# SCH_DTNEA-Z-AXIS-PRESS-MONITOR-TRANSMITT.net
KiCad netlist of a schematic drawn in EasyEDA
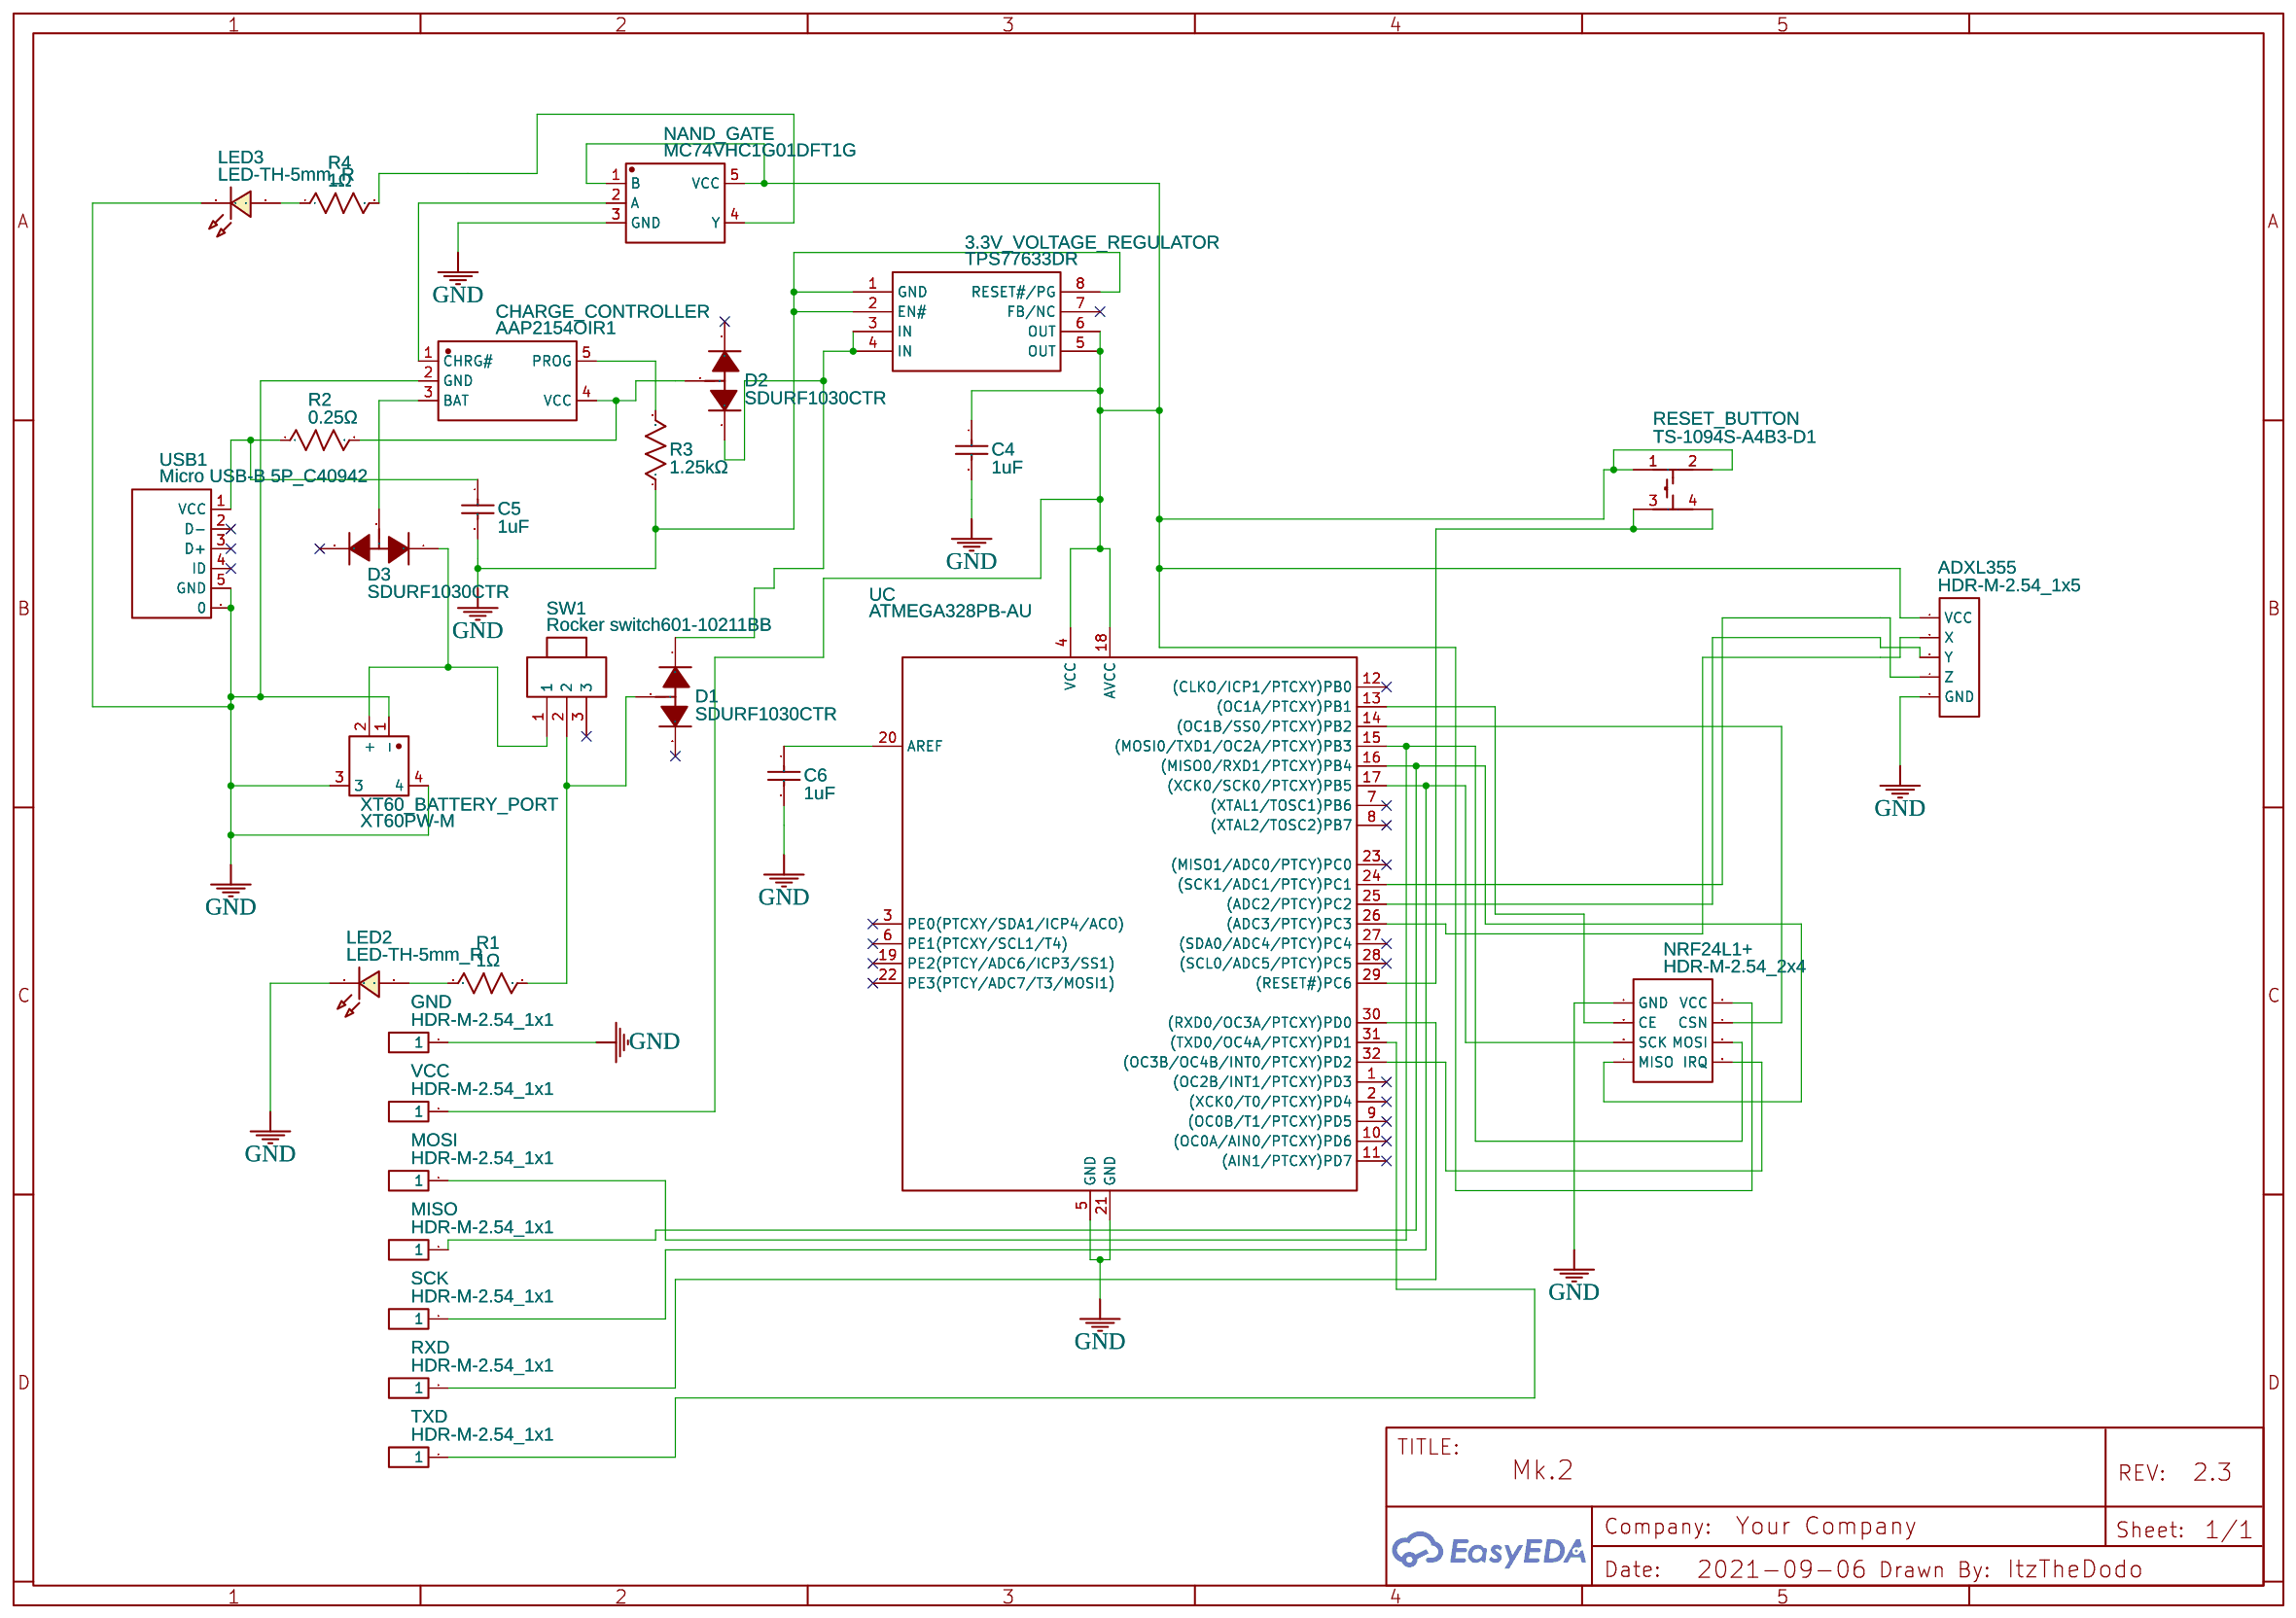
[diagram p0: schematic sheet]

(export (version "E")
  (design (tool "Eeschema 10.0.6"))
  (components
    (comp (ref "3.3V_VOLTAGE_REGULATOR")
      (value "TPS77633DR")
      (fields (field (name "BOM_Supplier Part") "C130078"))
      (libsource (lib "") (part "TPS77633DR"))
    )
    (comp (ref "ADXL355")
      (value "HDR-M-2.54_1x5")
      (fields (field (name "BOM_Supplier Part") "C358687"))
      (libsource (lib "") (part "HDR-M-2.54_1x5"))
    )
    (comp (ref "C4")
      (value "1uF")
      (fields
        (field (name "BOM_Manufacturer Part") "0603F105M250NT")
        (field (name "BOM_Supplier Part") "C36577")
      )
      (libsource (lib "") (part "0603F105M250NT"))
    )
    (comp (ref "C5")
      (value "1uF")
      (fields
        (field (name "BOM_Manufacturer Part") "0603F105M250NT")
        (field (name "BOM_Supplier Part") "C36577")
      )
      (libsource (lib "") (part "0603F105M250NT"))
    )
    (comp (ref "C6")
      (value "1uF")
      (fields
        (field (name "BOM_Manufacturer Part") "0603F105M250NT")
        (field (name "BOM_Supplier Part") "C36577")
      )
      (libsource (lib "") (part "0603F105M250NT"))
    )
    (comp (ref "CHARGE_CONTROLLER")
      (value "AAP2154OIR1")
      (fields (field (name "BOM_Supplier Part") "C370749"))
      (libsource (lib "") (part "AAP2154OIR1"))
    )
    (comp (ref "D1")
      (value "SDURF1030CTR")
      (fields (field (name "BOM_Supplier Part") "C260371"))
      (libsource (lib "") (part "SDURF1030CTR_1"))
    )
    (comp (ref "D2")
      (value "SDURF1030CTR")
      (fields (field (name "BOM_Supplier Part") "C260371"))
      (libsource (lib "") (part "SDURF1030CTR_1"))
    )
    (comp (ref "D3")
      (value "SDURF1030CTR")
      (fields (field (name "BOM_Supplier Part") "C260371"))
      (libsource (lib "") (part "SDURF1030CTR"))
    )
    (comp (ref "GND")
      (value "HDR-M-2.54_1x1")
      (fields (field (name "BOM_Supplier Part") "C81276"))
      (libsource (lib "") (part "HDR-M-2.54_1x1_3"))
    )
    (comp (ref "LED2")
      (value "LED-TH-5mm_R")
      (fields
        (field (name "BOM_Manufacturer Part") "333-2SURD/S530-A3")
        (field (name "BOM_Supplier Part") "C87271")
      )
      (libsource (lib "") (part "LED-TH-5mm_R"))
    )
    (comp (ref "LED3")
      (value "LED-TH-5mm_R")
      (fields
        (field (name "BOM_Manufacturer Part") "333-2SURD/S530-A3")
        (field (name "BOM_Supplier Part") "C87271")
      )
      (libsource (lib "") (part "LED-TH-5mm_R"))
    )
    (comp (ref "MISO")
      (value "HDR-M-2.54_1x1")
      (fields (field (name "BOM_Supplier Part") "C81276"))
      (libsource (lib "") (part "HDR-M-2.54_1x1_6"))
    )
    (comp (ref "MOSI")
      (value "HDR-M-2.54_1x1")
      (fields (field (name "BOM_Supplier Part") "C81276"))
      (libsource (lib "") (part "HDR-M-2.54_1x1"))
    )
    (comp (ref "NAND_GATE")
      (value "MC74VHC1G01DFT1G")
      (fields (field (name "BOM_Supplier Part") "C150244"))
      (libsource (lib "") (part "MC74VHC1G01DFT1G"))
    )
    (comp (ref "NRF24L1+")
      (value "HDR-M-2.54_2x4")
      (fields (field (name "BOM_Supplier Part") "C58363"))
      (libsource (lib "") (part "HDR-M-2.54_2x4"))
    )
    (comp (ref "R1") (value "1Ω") (libsource (lib "") (part "R_0603_US")))
    (comp (ref "R2") (value "0.25Ω") (libsource (lib "") (part "R_0603_US")))
    (comp (ref "R3") (value "1.25kΩ") (libsource (lib "") (part "R_0603_US_1")))
    (comp (ref "R4") (value "1Ω") (libsource (lib "") (part "R_0603_US")))
    (comp (ref "RESET_BUTTON")
      (value "TS-1094S-A4B3-D1")
      (fields (field (name "BOM_Supplier Part") "C492972"))
      (libsource (lib "") (part "TS-1094S-A4B3-D1"))
    )
    (comp (ref "RXD")
      (value "HDR-M-2.54_1x1")
      (fields (field (name "BOM_Supplier Part") "C81276"))
      (libsource (lib "") (part "HDR-M-2.54_1x1_2"))
    )
    (comp (ref "SCK")
      (value "HDR-M-2.54_1x1")
      (fields (field (name "BOM_Supplier Part") "C81276"))
      (libsource (lib "") (part "HDR-M-2.54_1x1_5"))
    )
    (comp (ref "SW1")
      (value "Rocker switch601-10211BB")
      (fields (field (name "BOM_Supplier Part") "C67849"))
      (libsource (lib "") (part "Rocker switch601-10211BB"))
    )
    (comp (ref "TXD")
      (value "HDR-M-2.54_1x1")
      (fields (field (name "BOM_Supplier Part") "C81276"))
      (libsource (lib "") (part "HDR-M-2.54_1x1_1"))
    )
    (comp (ref "UC")
      (value "ATMEGA328PB-AU")
      (fields (field (name "BOM_Supplier Part") "C132230"))
      (libsource (lib "") (part "ATMEGA328PB-AU"))
    )
    (comp (ref "USB1")
      (value "Micro USB-B 5P_C40942")
      (fields (field (name "BOM_Supplier Part") "C40942"))
      (libsource (lib "") (part "Micro USB-B 5P_C40942"))
    )
    (comp (ref "VCC")
      (value "HDR-M-2.54_1x1")
      (fields (field (name "BOM_Supplier Part") "C81276"))
      (libsource (lib "") (part "HDR-M-2.54_1x1_4"))
    )
    (comp (ref "XT60_BATTERY_PORT")
      (value "XT60PW-M")
      (fields (field (name "BOM_Supplier Part") "C98732"))
      (libsource (lib "") (part "XT60PW-M"))
    )
  )
  (nets
    (net (code "1") (name "GND") (class "Default")
      (node (ref "3.3V_VOLTAGE_REGULATOR") (pin "1") (pinfunction "GND_1") (pintype "passive"))
      (node (ref "3.3V_VOLTAGE_REGULATOR") (pin "2") (pinfunction "EN#_2") (pintype "unspecified"))
      (node (ref "3.3V_VOLTAGE_REGULATOR") (pin "8") (pinfunction "RESET#/PG_8") (pintype "unspecified"))
      (node (ref "ADXL355") (pin "5") (pinfunction "GND_5") (pintype "unspecified"))
      (node (ref "C4") (pin "2") (pinfunction "2_2") (pintype "input"))
      (node (ref "C5") (pin "2") (pinfunction "2_2") (pintype "input"))
      (node (ref "C6") (pin "2") (pinfunction "2_2") (pintype "input"))
      (node (ref "CHARGE_CONTROLLER") (pin "2") (pinfunction "GND_2") (pintype "unspecified"))
      (node (ref "GND") (pin "1") (pinfunction "1_1") (pintype "input"))
      (node (ref "LED2") (pin "2") (pinfunction "2_2") (pintype "unspecified"))
      (node (ref "LED3") (pin "2") (pinfunction "2_2") (pintype "unspecified"))
      (node (ref "NAND_GATE") (pin "3") (pinfunction "GND_3") (pintype "unspecified"))
      (node (ref "NRF24L1+") (pin "1") (pinfunction "GND_1") (pintype "unspecified"))
      (node (ref "R3") (pin "1") (pinfunction "1_1") (pintype "unspecified"))
      (node (ref "UC") (pin "21") (pinfunction "GND_21") (pintype "bidirectional"))
      (node (ref "UC") (pin "5") (pinfunction "GND_5") (pintype "bidirectional"))
      (node (ref "USB1") (pin "0") (pinfunction "0_0") (pintype "input"))
      (node (ref "USB1") (pin "5") (pinfunction "GND_5") (pintype "input"))
      (node (ref "XT60_BATTERY_PORT") (pin "1") (pinfunction "-_1") (pintype "unspecified"))
      (node (ref "XT60_BATTERY_PORT") (pin "3") (pinfunction "3_3") (pintype "unspecified"))
      (node (ref "XT60_BATTERY_PORT") (pin "4") (pinfunction "4_4") (pintype "unspecified"))
    )
    (net (code "2") (name "Net-(3.3V_VOLTAGE_REGULATOR-IN-Pad3)") (class "Default")
      (node (ref "3.3V_VOLTAGE_REGULATOR") (pin "3") (pinfunction "IN_3") (pintype "passive"))
      (node (ref "3.3V_VOLTAGE_REGULATOR") (pin "4") (pinfunction "IN_4") (pintype "passive"))
      (node (ref "D1") (pin "1") (pinfunction "C_1") (pintype "unspecified"))
      (node (ref "D2") (pin "3") (pinfunction "C_3") (pintype "unspecified"))
    )
    (net (code "3") (name "Net-(ADXL355-VCC)") (class "Default")
      (node (ref "3.3V_VOLTAGE_REGULATOR") (pin "5") (pinfunction "OUT_5") (pintype "passive"))
      (node (ref "3.3V_VOLTAGE_REGULATOR") (pin "6") (pinfunction "OUT_6") (pintype "passive"))
      (node (ref "ADXL355") (pin "1") (pinfunction "VCC_1") (pintype "unspecified"))
      (node (ref "C4") (pin "1") (pinfunction "1_1") (pintype "input"))
      (node (ref "NAND_GATE") (pin "1") (pinfunction "B_1") (pintype "unspecified"))
      (node (ref "NAND_GATE") (pin "5") (pinfunction "VCC_5") (pintype "unspecified"))
      (node (ref "NRF24L1+") (pin "2") (pinfunction "VCC_2") (pintype "unspecified"))
      (node (ref "RESET_BUTTON") (pin "1") (pinfunction "1_1") (pintype "unspecified"))
      (node (ref "RESET_BUTTON") (pin "2") (pinfunction "2_2") (pintype "unspecified"))
      (node (ref "UC") (pin "18") (pinfunction "AVCC_18") (pintype "bidirectional"))
      (node (ref "UC") (pin "4") (pinfunction "VCC_4") (pintype "bidirectional"))
      (node (ref "VCC") (pin "1") (pinfunction "1_1") (pintype "input"))
    )
    (net (code "4") (name "Net-(ADXL355-X)") (class "Default")
      (node (ref "ADXL355") (pin "2") (pinfunction "X_2") (pintype "unspecified"))
      (node (ref "UC") (pin "26") (pinfunction "(ADC3/PTCY)PC3_26") (pintype "bidirectional"))
    )
    (net (code "5") (name "Net-(ADXL355-Y)") (class "Default")
      (node (ref "ADXL355") (pin "3") (pinfunction "Y_3") (pintype "unspecified"))
      (node (ref "UC") (pin "25") (pinfunction "(ADC2/PTCY)PC2_25") (pintype "bidirectional"))
    )
    (net (code "6") (name "Net-(ADXL355-Z)") (class "Default")
      (node (ref "ADXL355") (pin "4") (pinfunction "Z_4") (pintype "unspecified"))
      (node (ref "UC") (pin "24") (pinfunction "(SCK1/ADC1/PTCY)PC1_24") (pintype "bidirectional"))
    )
    (net (code "7") (name "Net-(CHARGE_CONTROLLER-BAT)") (class "Default")
      (node (ref "CHARGE_CONTROLLER") (pin "3") (pinfunction "BAT_3") (pintype "unspecified"))
      (node (ref "D3") (pin "2") (pinfunction "A_2") (pintype "unspecified"))
    )
    (net (code "8") (name "Net-(CHARGE_CONTROLLER-CHRG#)") (class "Default")
      (node (ref "CHARGE_CONTROLLER") (pin "1") (pinfunction "CHRG#_1") (pintype "unspecified"))
      (node (ref "NAND_GATE") (pin "2") (pinfunction "A_2") (pintype "unspecified"))
    )
    (net (code "9") (name "Net-(CHARGE_CONTROLLER-PROG)") (class "Default")
      (node (ref "CHARGE_CONTROLLER") (pin "5") (pinfunction "PROG_5") (pintype "unspecified"))
      (node (ref "R3") (pin "2") (pinfunction "2_2") (pintype "unspecified"))
    )
    (net (code "10") (name "Net-(CHARGE_CONTROLLER-VCC)") (class "Default")
      (node (ref "CHARGE_CONTROLLER") (pin "4") (pinfunction "VCC_4") (pintype "unspecified"))
      (node (ref "D2") (pin "2") (pinfunction "A_2") (pintype "unspecified"))
      (node (ref "R2") (pin "2") (pinfunction "2_2") (pintype "unspecified"))
    )
    (net (code "11") (name "Net-(D1-A)") (class "Default")
      (node (ref "D1") (pin "2") (pinfunction "A_2") (pintype "unspecified"))
      (node (ref "R1") (pin "2") (pinfunction "2_2") (pintype "unspecified"))
      (node (ref "SW1") (pin "2") (pinfunction "2_2") (pintype "unspecified"))
    )
    (net (code "12") (name "Net-(LED2-Pad1)") (class "Default")
      (node (ref "LED2") (pin "1") (pinfunction "1_1") (pintype "unspecified"))
      (node (ref "R1") (pin "1") (pinfunction "1_1") (pintype "unspecified"))
    )
    (net (code "13") (name "Net-(LED3-Pad1)") (class "Default")
      (node (ref "LED3") (pin "1") (pinfunction "1_1") (pintype "unspecified"))
      (node (ref "R4") (pin "1") (pinfunction "1_1") (pintype "unspecified"))
    )
    (net (code "14") (name "Net-(NAND_GATE-Y)") (class "Default")
      (node (ref "NAND_GATE") (pin "4") (pinfunction "Y_4") (pintype "unspecified"))
      (node (ref "R4") (pin "2") (pinfunction "2_2") (pintype "unspecified"))
    )
    (net (code "15") (name "Net-(NRF24L1+-CE)") (class "Default")
      (node (ref "NRF24L1+") (pin "3") (pinfunction "CE_3") (pintype "unspecified"))
      (node (ref "UC") (pin "13") (pinfunction "(OC1A/PTCXY)PB1_13") (pintype "bidirectional"))
    )
    (net (code "16") (name "Net-(NRF24L1+-CSN)") (class "Default")
      (node (ref "NRF24L1+") (pin "4") (pinfunction "CSN_4") (pintype "unspecified"))
      (node (ref "UC") (pin "14") (pinfunction "(OC1B/SS0/PTCXY)PB2_14") (pintype "bidirectional"))
    )
    (net (code "17") (name "Net-(NRF24L1+-IRQ)") (class "Default")
      (node (ref "NRF24L1+") (pin "8") (pinfunction "IRQ_8") (pintype "unspecified"))
      (node (ref "UC") (pin "32") (pinfunction "(OC3B/OC4B/INT0/PTCXY)PD2_32") (pintype "bidirectional"))
    )
    (net (code "18") (name "Net-(NRF24L1+-MISO)") (class "Default")
      (node (ref "MISO") (pin "1") (pinfunction "1_1") (pintype "input"))
      (node (ref "NRF24L1+") (pin "7") (pinfunction "MISO_7") (pintype "unspecified"))
      (node (ref "UC") (pin "16") (pinfunction "(MISO0/RXD1/PTCXY)PB4_16") (pintype "bidirectional"))
    )
    (net (code "19") (name "Net-(NRF24L1+-MOSI)") (class "Default")
      (node (ref "MOSI") (pin "1") (pinfunction "1_1") (pintype "input"))
      (node (ref "NRF24L1+") (pin "6") (pinfunction "MOSI_6") (pintype "unspecified"))
      (node (ref "UC") (pin "15") (pinfunction "(MOSI0/TXD1/OC2A/PTCXY)PB3_15") (pintype "bidirectional"))
    )
    (net (code "20") (name "Net-(NRF24L1+-SCK)") (class "Default")
      (node (ref "NRF24L1+") (pin "5") (pinfunction "SCK_5") (pintype "unspecified"))
      (node (ref "SCK") (pin "1") (pinfunction "1_1") (pintype "input"))
      (node (ref "UC") (pin "17") (pinfunction "(XCK0/SCK0/PTCXY)PB5_17") (pintype "bidirectional"))
    )
    (net (code "21") (name "Net-(UC-(RESET#)PC6)") (class "Default")
      (node (ref "RESET_BUTTON") (pin "3") (pinfunction "3_3") (pintype "unspecified"))
      (node (ref "RESET_BUTTON") (pin "4") (pinfunction "4_4") (pintype "unspecified"))
      (node (ref "UC") (pin "29") (pinfunction "(RESET#)PC6_29") (pintype "bidirectional"))
    )
    (net (code "22") (name "Net-(UC-(RXD0{slash}OC3A{slash}PTCXY)PD0)") (class "Default")
      (node (ref "RXD") (pin "1") (pinfunction "1_1") (pintype "input"))
      (node (ref "UC") (pin "30") (pinfunction "(RXD0/OC3A/PTCXY)PD0_30") (pintype "bidirectional"))
    )
    (net (code "23") (name "Net-(UC-(TXD0{slash}OC4A{slash}PTCXY)PD1)") (class "Default")
      (node (ref "TXD") (pin "1") (pinfunction "1_1") (pintype "input"))
      (node (ref "UC") (pin "31") (pinfunction "(TXD0/OC4A/PTCXY)PD1_31") (pintype "bidirectional"))
    )
    (net (code "24") (name "Net-(UC-AREF)") (class "Default")
      (node (ref "C6") (pin "1") (pinfunction "1_1") (pintype "input"))
      (node (ref "UC") (pin "20") (pinfunction "AREF_20") (pintype "bidirectional"))
    )
    (net (code "25") (name "Net-(USB1-VCC)") (class "Default")
      (node (ref "C5") (pin "1") (pinfunction "1_1") (pintype "input"))
      (node (ref "R2") (pin "1") (pinfunction "1_1") (pintype "unspecified"))
      (node (ref "USB1") (pin "1") (pinfunction "VCC_1") (pintype "input"))
    )
    (net (code "26") (name "Net-(XT60_BATTERY_PORT-+)") (class "Default")
      (node (ref "D3") (pin "1") (pinfunction "C_1") (pintype "unspecified"))
      (node (ref "SW1") (pin "1") (pinfunction "1_1") (pintype "unspecified"))
      (node (ref "XT60_BATTERY_PORT") (pin "2") (pinfunction "+_2") (pintype "unspecified"))
    )
    (net (code "27") (name "unconnected-(3.3V_VOLTAGE_REGULATOR-FB{slash}NC-Pad7)") (class "Default")
      (node (ref "3.3V_VOLTAGE_REGULATOR") (pin "7") (pinfunction "FB/NC_7") (pintype "unspecified+no_connect"))
    )
    (net (code "28") (name "unconnected-(D1-C-Pad3)") (class "Default")
      (node (ref "D1") (pin "3") (pinfunction "C_3") (pintype "unspecified+no_connect"))
    )
    (net (code "29") (name "unconnected-(D2-C-Pad1)") (class "Default")
      (node (ref "D2") (pin "1") (pinfunction "C_1") (pintype "unspecified+no_connect"))
    )
    (net (code "30") (name "unconnected-(D3-C-Pad3)") (class "Default")
      (node (ref "D3") (pin "3") (pinfunction "C_3") (pintype "unspecified+no_connect"))
    )
    (net (code "31") (name "unconnected-(SW1-Pad3)") (class "Default")
      (node (ref "SW1") (pin "3") (pinfunction "3_3") (pintype "unspecified+no_connect"))
    )
    (net (code "32") (name "unconnected-(UC-(AIN1{slash}PTCXY)PD7-Pad11)") (class "Default")
      (node (ref "UC") (pin "11") (pinfunction "(AIN1/PTCXY)PD7_11") (pintype "bidirectional+no_connect"))
    )
    (net (code "33") (name "unconnected-(UC-(CLKO{slash}ICP1{slash}PTCXY)PB0-Pad12)") (class "Default")
      (node (ref "UC") (pin "12") (pinfunction "(CLKO/ICP1/PTCXY)PB0_12") (pintype "bidirectional+no_connect"))
    )
    (net (code "34") (name "unconnected-(UC-(MISO1{slash}ADC0{slash}PTCY)PC0-Pad23)") (class "Default")
      (node (ref "UC") (pin "23") (pinfunction "(MISO1/ADC0/PTCY)PC0_23") (pintype "bidirectional+no_connect"))
    )
    (net (code "35") (name "unconnected-(UC-(OC0A{slash}AIN0{slash}PTCXY)PD6-Pad10)") (class "Default")
      (node (ref "UC") (pin "10") (pinfunction "(OC0A/AIN0/PTCXY)PD6_10") (pintype "bidirectional+no_connect"))
    )
    (net (code "36") (name "unconnected-(UC-(OC0B{slash}T1{slash}PTCXY)PD5-Pad9)") (class "Default")
      (node (ref "UC") (pin "9") (pinfunction "(OC0B/T1/PTCXY)PD5_9") (pintype "bidirectional+no_connect"))
    )
    (net (code "37") (name "unconnected-(UC-(OC2B{slash}INT1{slash}PTCXY)PD3-Pad1)") (class "Default")
      (node (ref "UC") (pin "1") (pinfunction "(OC2B/INT1/PTCXY)PD3_1") (pintype "bidirectional+no_connect"))
    )
    (net (code "38") (name "unconnected-(UC-(SCL0{slash}ADC5{slash}PTCY)PC5-Pad28)") (class "Default")
      (node (ref "UC") (pin "28") (pinfunction "(SCL0/ADC5/PTCY)PC5_28") (pintype "bidirectional+no_connect"))
    )
    (net (code "39") (name "unconnected-(UC-(SDA0{slash}ADC4{slash}PTCY)PC4-Pad27)") (class "Default")
      (node (ref "UC") (pin "27") (pinfunction "(SDA0/ADC4/PTCY)PC4_27") (pintype "bidirectional+no_connect"))
    )
    (net (code "40") (name "unconnected-(UC-(XCK0{slash}T0{slash}PTCXY)PD4-Pad2)") (class "Default")
      (node (ref "UC") (pin "2") (pinfunction "(XCK0/T0/PTCXY)PD4_2") (pintype "bidirectional+no_connect"))
    )
    (net (code "41") (name "unconnected-(UC-(XTAL1{slash}TOSC1)PB6-Pad7)") (class "Default")
      (node (ref "UC") (pin "7") (pinfunction "(XTAL1/TOSC1)PB6_7") (pintype "bidirectional+no_connect"))
    )
    (net (code "42") (name "unconnected-(UC-(XTAL2{slash}TOSC2)PB7-Pad8)") (class "Default")
      (node (ref "UC") (pin "8") (pinfunction "(XTAL2/TOSC2)PB7_8") (pintype "bidirectional+no_connect"))
    )
    (net (code "43") (name "unconnected-(UC-PE0(PTCXY{slash}SDA1{slash}ICP4{slash}ACO)-Pad3)") (class "Default")
      (node (ref "UC") (pin "3") (pinfunction "PE0(PTCXY/SDA1/ICP4/ACO)_3") (pintype "bidirectional+no_connect"))
    )
    (net (code "44") (name "unconnected-(UC-PE1(PTCXY{slash}SCL1{slash}T4)-Pad6)") (class "Default")
      (node (ref "UC") (pin "6") (pinfunction "PE1(PTCXY/SCL1/T4)_6") (pintype "bidirectional+no_connect"))
    )
    (net (code "45") (name "unconnected-(UC-PE2(PTCY{slash}ADC6{slash}ICP3{slash}SS1)-Pad19)") (class "Default")
      (node (ref "UC") (pin "19") (pinfunction "PE2(PTCY/ADC6/ICP3/SS1)_19") (pintype "bidirectional+no_connect"))
    )
    (net (code "46") (name "unconnected-(UC-PE3(PTCY{slash}ADC7{slash}T3{slash}MOSI1)-Pad22)") (class "Default")
      (node (ref "UC") (pin "22") (pinfunction "PE3(PTCY/ADC7/T3/MOSI1)_22") (pintype "bidirectional+no_connect"))
    )
    (net (code "47") (name "unconnected-(USB1-D+-Pad3)") (class "Default")
      (node (ref "USB1") (pin "3") (pinfunction "D+_3") (pintype "input+no_connect"))
    )
    (net (code "48") (name "unconnected-(USB1-D--Pad2)") (class "Default")
      (node (ref "USB1") (pin "2") (pinfunction "D-_2") (pintype "input+no_connect"))
    )
    (net (code "49") (name "unconnected-(USB1-ID-Pad4)") (class "Default")
      (node (ref "USB1") (pin "4") (pinfunction "ID_4") (pintype "input+no_connect"))
    )
  )
)
